# DCMotorControl_v01.net
KiCad netlist of a schematic drawn in EAGLE
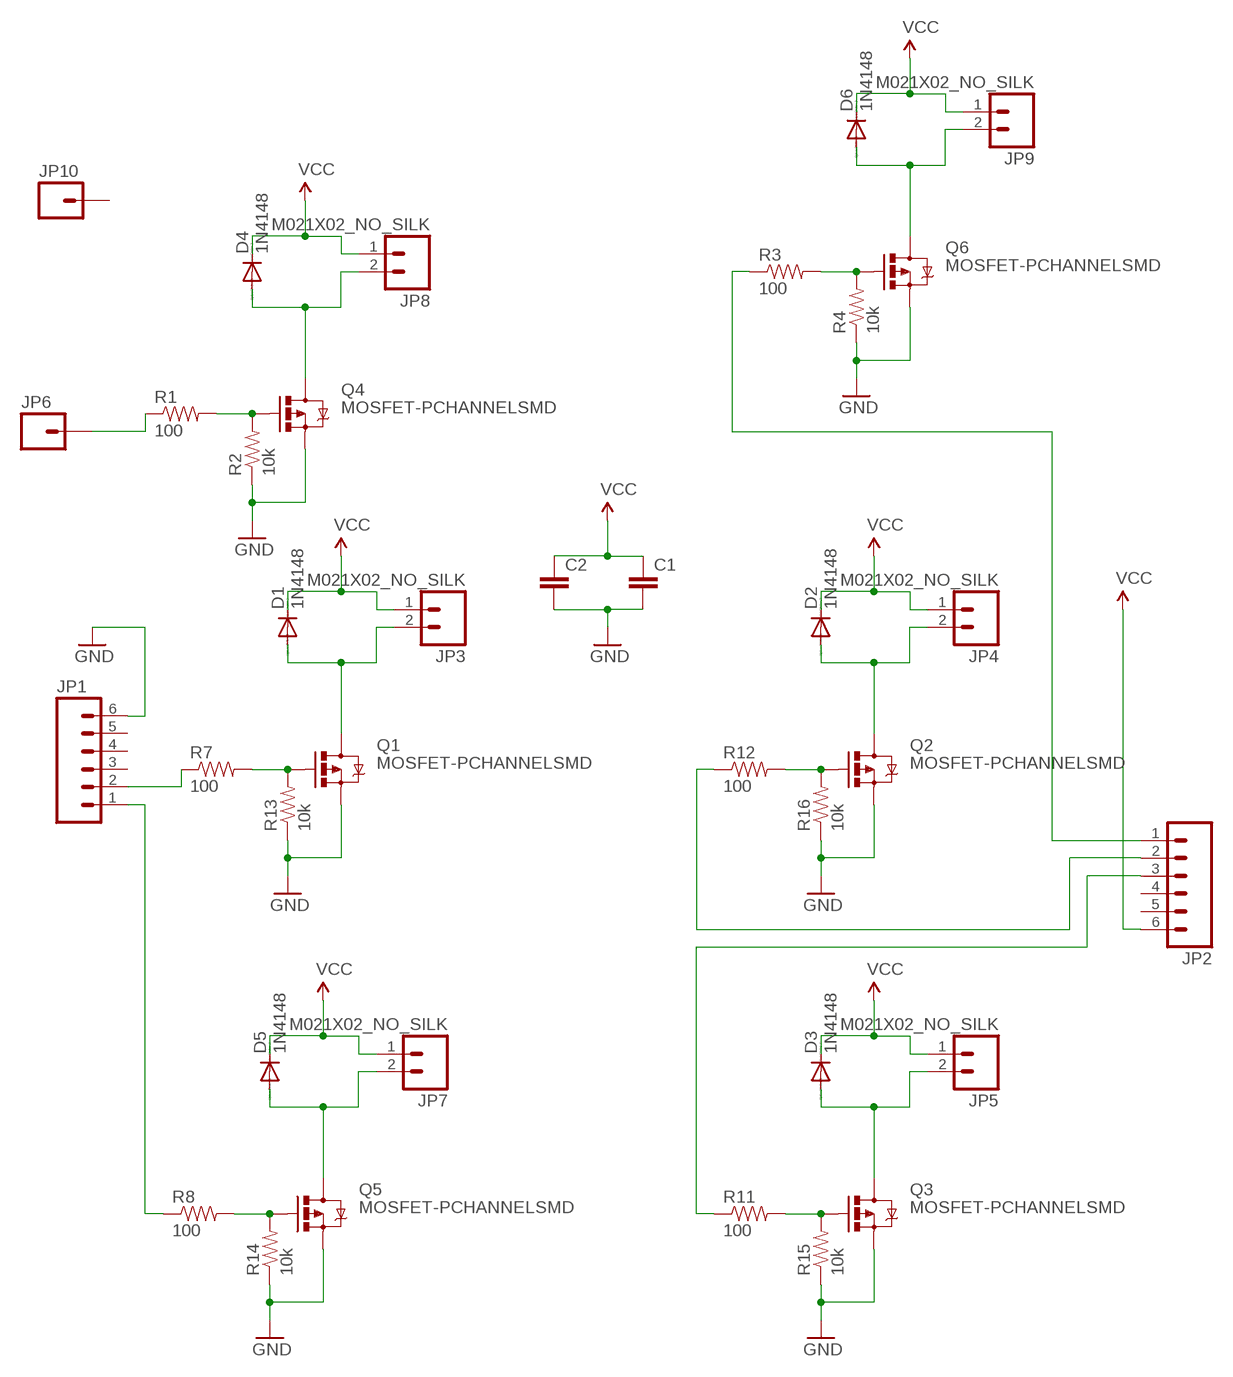
[diagram p0: schematic, sheet 1]

(export (version "E")
  (design (tool "Eeschema 10.0.6"))
  (components
    (comp (ref "C1")
      (value "CAP0805")
      (footprint "eagle-import:0805")
      (libsource (lib "eagle-import") (part "CAP0805"))
    )
    (comp (ref "C2")
      (value "CAP0805")
      (footprint "eagle-import:0805")
      (libsource (lib "eagle-import") (part "CAP0805"))
    )
    (comp (ref "D1")
      (value "1N4148")
      (footprint "eagle-import:SOD323-R")
      (libsource (lib "eagle-import") (part "DIODE-SOD323-R"))
    )
    (comp (ref "D2")
      (value "1N4148")
      (footprint "eagle-import:SOD323-R")
      (libsource (lib "eagle-import") (part "DIODE-SOD323-R"))
    )
    (comp (ref "D3")
      (value "1N4148")
      (footprint "eagle-import:SOD323-R")
      (libsource (lib "eagle-import") (part "DIODE-SOD323-R"))
    )
    (comp (ref "D4")
      (value "1N4148")
      (footprint "eagle-import:SOD323-R")
      (libsource (lib "eagle-import") (part "DIODE-SOD323-R"))
    )
    (comp (ref "D5")
      (value "1N4148")
      (footprint "eagle-import:SOD323-R")
      (libsource (lib "eagle-import") (part "DIODE-SOD323-R"))
    )
    (comp (ref "D6")
      (value "1N4148")
      (footprint "eagle-import:SOD323-R")
      (libsource (lib "eagle-import") (part "DIODE-SOD323-R"))
    )
    (comp (ref "JP1")
      (value "M06NO_SILK")
      (footprint "eagle-import:1X06_NO_SILK")
      (libsource (lib "eagle-import") (part "M06NO_SILK"))
    )
    (comp (ref "JP2")
      (value "M06NO_SILK")
      (footprint "eagle-import:1X06_NO_SILK")
      (libsource (lib "eagle-import") (part "M06NO_SILK"))
    )
    (comp (ref "JP3")
      (value "M021X02_NO_SILK")
      (footprint "eagle-import:1X02_NO_SILK")
      (libsource (lib "eagle-import") (part "M021X02_NO_SILK"))
    )
    (comp (ref "JP4")
      (value "M021X02_NO_SILK")
      (footprint "eagle-import:1X02_NO_SILK")
      (libsource (lib "eagle-import") (part "M021X02_NO_SILK"))
    )
    (comp (ref "JP5")
      (value "M021X02_NO_SILK")
      (footprint "eagle-import:1X02_NO_SILK")
      (libsource (lib "eagle-import") (part "M021X02_NO_SILK"))
    )
    (comp (ref "JP6")
      (value "M01NOSILK-KIT")
      (footprint "eagle-import:1X01NS-KIT")
      (libsource (lib "eagle-import") (part "M01NOSILK-KIT"))
    )
    (comp (ref "JP7")
      (value "M021X02_NO_SILK")
      (footprint "eagle-import:1X02_NO_SILK")
      (libsource (lib "eagle-import") (part "M021X02_NO_SILK"))
    )
    (comp (ref "JP8")
      (value "M021X02_NO_SILK")
      (footprint "eagle-import:1X02_NO_SILK")
      (libsource (lib "eagle-import") (part "M021X02_NO_SILK"))
    )
    (comp (ref "JP9")
      (value "M021X02_NO_SILK")
      (footprint "eagle-import:1X02_NO_SILK")
      (libsource (lib "eagle-import") (part "M021X02_NO_SILK"))
    )
    (comp (ref "JP10")
      (value "M01NOSILK-KIT")
      (footprint "eagle-import:1X01NS-KIT")
      (libsource (lib "eagle-import") (part "M01NOSILK-KIT"))
    )
    (comp (ref "Q1")
      (value "MOSFET-PCHANNELSMD")
      (footprint "eagle-import:SOT23-3")
      (libsource (lib "eagle-import") (part "MOSFET-PCHANNELSMD"))
    )
    (comp (ref "Q2")
      (value "MOSFET-PCHANNELSMD")
      (footprint "eagle-import:SOT23-3")
      (libsource (lib "eagle-import") (part "MOSFET-PCHANNELSMD"))
    )
    (comp (ref "Q3")
      (value "MOSFET-PCHANNELSMD")
      (footprint "eagle-import:SOT23-3")
      (libsource (lib "eagle-import") (part "MOSFET-PCHANNELSMD"))
    )
    (comp (ref "Q4")
      (value "MOSFET-PCHANNELSMD")
      (footprint "eagle-import:SOT23-3")
      (libsource (lib "eagle-import") (part "MOSFET-PCHANNELSMD"))
    )
    (comp (ref "Q5")
      (value "MOSFET-PCHANNELSMD")
      (footprint "eagle-import:SOT23-3")
      (libsource (lib "eagle-import") (part "MOSFET-PCHANNELSMD"))
    )
    (comp (ref "Q6")
      (value "MOSFET-PCHANNELSMD")
      (footprint "eagle-import:SOT23-3")
      (libsource (lib "eagle-import") (part "MOSFET-PCHANNELSMD"))
    )
    (comp (ref "R1")
      (value "100")
      (footprint "eagle-import:0603-RES")
      (libsource (lib "eagle-import") (part "RESISTOR0603-RES"))
    )
    (comp (ref "R2")
      (value "10k")
      (footprint "eagle-import:0603-RES")
      (libsource (lib "eagle-import") (part "RESISTOR0603-RES"))
    )
    (comp (ref "R3")
      (value "100")
      (footprint "eagle-import:0603-RES")
      (libsource (lib "eagle-import") (part "RESISTOR0603-RES"))
    )
    (comp (ref "R4")
      (value "10k")
      (footprint "eagle-import:0603-RES")
      (libsource (lib "eagle-import") (part "RESISTOR0603-RES"))
    )
    (comp (ref "R7")
      (value "100")
      (footprint "eagle-import:0603-RES")
      (libsource (lib "eagle-import") (part "RESISTOR0603-RES"))
    )
    (comp (ref "R8")
      (value "100")
      (footprint "eagle-import:0603-RES")
      (libsource (lib "eagle-import") (part "RESISTOR0603-RES"))
    )
    (comp (ref "R11")
      (value "100")
      (footprint "eagle-import:0603-RES")
      (libsource (lib "eagle-import") (part "RESISTOR0603-RES"))
    )
    (comp (ref "R12")
      (value "100")
      (footprint "eagle-import:0603-RES")
      (libsource (lib "eagle-import") (part "RESISTOR0603-RES"))
    )
    (comp (ref "R13")
      (value "10k")
      (footprint "eagle-import:0603-RES")
      (libsource (lib "eagle-import") (part "RESISTOR0603-RES"))
    )
    (comp (ref "R14")
      (value "10k")
      (footprint "eagle-import:0603-RES")
      (libsource (lib "eagle-import") (part "RESISTOR0603-RES"))
    )
    (comp (ref "R15")
      (value "10k")
      (footprint "eagle-import:0603-RES")
      (libsource (lib "eagle-import") (part "RESISTOR0603-RES"))
    )
    (comp (ref "R16")
      (value "10k")
      (footprint "eagle-import:0603-RES")
      (libsource (lib "eagle-import") (part "RESISTOR0603-RES"))
    )
  )
  (nets
    (net (code "1") (name "GND") (class "Default")
      (node (ref "C1") (pin "2") (pinfunction "2_2") (pintype "passive"))
      (node (ref "C2") (pin "2") (pinfunction "2_2") (pintype "passive"))
      (node (ref "JP1") (pin "6") (pinfunction "6_6") (pintype "passive"))
      (node (ref "Q1") (pin "2") (pinfunction "S_2") (pintype "passive"))
      (node (ref "Q2") (pin "2") (pinfunction "S_2") (pintype "passive"))
      (node (ref "Q3") (pin "2") (pinfunction "S_2") (pintype "passive"))
      (node (ref "Q4") (pin "2") (pinfunction "S_2") (pintype "passive"))
      (node (ref "Q5") (pin "2") (pinfunction "S_2") (pintype "passive"))
      (node (ref "Q6") (pin "2") (pinfunction "S_2") (pintype "passive"))
      (node (ref "R13") (pin "1") (pinfunction "1_1") (pintype "passive"))
      (node (ref "R14") (pin "1") (pinfunction "1_1") (pintype "passive"))
      (node (ref "R15") (pin "1") (pinfunction "1_1") (pintype "passive"))
      (node (ref "R16") (pin "1") (pinfunction "1_1") (pintype "passive"))
      (node (ref "R2") (pin "1") (pinfunction "1_1") (pintype "passive"))
      (node (ref "R4") (pin "1") (pinfunction "1_1") (pintype "passive"))
    )
    (net (code "2") (name "Net-(JP1-Pad1)") (class "Default")
      (node (ref "JP1") (pin "1") (pinfunction "1_1") (pintype "passive"))
      (node (ref "R8") (pin "1") (pinfunction "1_1") (pintype "passive"))
    )
    (net (code "3") (name "Net-(JP1-Pad2)") (class "Default")
      (node (ref "JP1") (pin "2") (pinfunction "2_2") (pintype "passive"))
      (node (ref "R7") (pin "1") (pinfunction "1_1") (pintype "passive"))
    )
    (net (code "4") (name "Net-(JP2-Pad1)") (class "Default")
      (node (ref "JP2") (pin "1") (pinfunction "1_1") (pintype "passive"))
      (node (ref "R3") (pin "1") (pinfunction "1_1") (pintype "passive"))
    )
    (net (code "5") (name "Net-(JP2-Pad2)") (class "Default")
      (node (ref "JP2") (pin "2") (pinfunction "2_2") (pintype "passive"))
      (node (ref "R12") (pin "1") (pinfunction "1_1") (pintype "passive"))
    )
    (net (code "6") (name "Net-(JP2-Pad3)") (class "Default")
      (node (ref "JP2") (pin "3") (pinfunction "3_3") (pintype "passive"))
      (node (ref "R11") (pin "1") (pinfunction "1_1") (pintype "passive"))
    )
    (net (code "7") (name "Net-(JP6-Pad1)") (class "Default")
      (node (ref "JP6") (pin "1") (pinfunction "1_1") (pintype "passive"))
      (node (ref "R1") (pin "1") (pinfunction "1_1") (pintype "passive"))
    )
    (net (code "8") (name "Net-(Q1-D)") (class "Default")
      (node (ref "D1") (pin "A") (pinfunction "A_A") (pintype "passive"))
      (node (ref "JP3") (pin "2") (pinfunction "2_2") (pintype "passive"))
      (node (ref "Q1") (pin "3") (pinfunction "D_3") (pintype "passive"))
    )
    (net (code "9") (name "Net-(Q1-G)") (class "Default")
      (node (ref "Q1") (pin "1") (pinfunction "G_1") (pintype "passive"))
      (node (ref "R13") (pin "2") (pinfunction "2_2") (pintype "passive"))
      (node (ref "R7") (pin "2") (pinfunction "2_2") (pintype "passive"))
    )
    (net (code "10") (name "Net-(Q2-D)") (class "Default")
      (node (ref "D2") (pin "A") (pinfunction "A_A") (pintype "passive"))
      (node (ref "JP4") (pin "2") (pinfunction "2_2") (pintype "passive"))
      (node (ref "Q2") (pin "3") (pinfunction "D_3") (pintype "passive"))
    )
    (net (code "11") (name "Net-(Q2-G)") (class "Default")
      (node (ref "Q2") (pin "1") (pinfunction "G_1") (pintype "passive"))
      (node (ref "R12") (pin "2") (pinfunction "2_2") (pintype "passive"))
      (node (ref "R16") (pin "2") (pinfunction "2_2") (pintype "passive"))
    )
    (net (code "12") (name "Net-(Q3-D)") (class "Default")
      (node (ref "D3") (pin "A") (pinfunction "A_A") (pintype "passive"))
      (node (ref "JP5") (pin "2") (pinfunction "2_2") (pintype "passive"))
      (node (ref "Q3") (pin "3") (pinfunction "D_3") (pintype "passive"))
    )
    (net (code "13") (name "Net-(Q3-G)") (class "Default")
      (node (ref "Q3") (pin "1") (pinfunction "G_1") (pintype "passive"))
      (node (ref "R11") (pin "2") (pinfunction "2_2") (pintype "passive"))
      (node (ref "R15") (pin "2") (pinfunction "2_2") (pintype "passive"))
    )
    (net (code "14") (name "Net-(Q4-D)") (class "Default")
      (node (ref "D4") (pin "A") (pinfunction "A_A") (pintype "passive"))
      (node (ref "JP8") (pin "2") (pinfunction "2_2") (pintype "passive"))
      (node (ref "Q4") (pin "3") (pinfunction "D_3") (pintype "passive"))
    )
    (net (code "15") (name "Net-(Q4-G)") (class "Default")
      (node (ref "Q4") (pin "1") (pinfunction "G_1") (pintype "passive"))
      (node (ref "R1") (pin "2") (pinfunction "2_2") (pintype "passive"))
      (node (ref "R2") (pin "2") (pinfunction "2_2") (pintype "passive"))
    )
    (net (code "16") (name "Net-(Q5-D)") (class "Default")
      (node (ref "D5") (pin "A") (pinfunction "A_A") (pintype "passive"))
      (node (ref "JP7") (pin "2") (pinfunction "2_2") (pintype "passive"))
      (node (ref "Q5") (pin "3") (pinfunction "D_3") (pintype "passive"))
    )
    (net (code "17") (name "Net-(Q5-G)") (class "Default")
      (node (ref "Q5") (pin "1") (pinfunction "G_1") (pintype "passive"))
      (node (ref "R14") (pin "2") (pinfunction "2_2") (pintype "passive"))
      (node (ref "R8") (pin "2") (pinfunction "2_2") (pintype "passive"))
    )
    (net (code "18") (name "Net-(Q6-D)") (class "Default")
      (node (ref "D6") (pin "A") (pinfunction "A_A") (pintype "passive"))
      (node (ref "JP9") (pin "2") (pinfunction "2_2") (pintype "passive"))
      (node (ref "Q6") (pin "3") (pinfunction "D_3") (pintype "passive"))
    )
    (net (code "19") (name "Net-(Q6-G)") (class "Default")
      (node (ref "Q6") (pin "1") (pinfunction "G_1") (pintype "passive"))
      (node (ref "R3") (pin "2") (pinfunction "2_2") (pintype "passive"))
      (node (ref "R4") (pin "2") (pinfunction "2_2") (pintype "passive"))
    )
    (net (code "20") (name "VCC") (class "Default")
      (node (ref "C1") (pin "1") (pinfunction "1_1") (pintype "passive"))
      (node (ref "C2") (pin "1") (pinfunction "1_1") (pintype "passive"))
      (node (ref "D1") (pin "C") (pinfunction "C_C") (pintype "passive"))
      (node (ref "D2") (pin "C") (pinfunction "C_C") (pintype "passive"))
      (node (ref "D3") (pin "C") (pinfunction "C_C") (pintype "passive"))
      (node (ref "D4") (pin "C") (pinfunction "C_C") (pintype "passive"))
      (node (ref "D5") (pin "C") (pinfunction "C_C") (pintype "passive"))
      (node (ref "D6") (pin "C") (pinfunction "C_C") (pintype "passive"))
      (node (ref "JP2") (pin "6") (pinfunction "6_6") (pintype "passive"))
      (node (ref "JP3") (pin "1") (pinfunction "1_1") (pintype "passive"))
      (node (ref "JP4") (pin "1") (pinfunction "1_1") (pintype "passive"))
      (node (ref "JP5") (pin "1") (pinfunction "1_1") (pintype "passive"))
      (node (ref "JP7") (pin "1") (pinfunction "1_1") (pintype "passive"))
      (node (ref "JP8") (pin "1") (pinfunction "1_1") (pintype "passive"))
      (node (ref "JP9") (pin "1") (pinfunction "1_1") (pintype "passive"))
    )
    (net (code "21") (name "unconnected-(JP1-Pad3)") (class "Default")
      (node (ref "JP1") (pin "3") (pinfunction "3_3") (pintype "passive"))
    )
    (net (code "22") (name "unconnected-(JP1-Pad4)") (class "Default")
      (node (ref "JP1") (pin "4") (pinfunction "4_4") (pintype "passive"))
    )
    (net (code "23") (name "unconnected-(JP1-Pad5)") (class "Default")
      (node (ref "JP1") (pin "5") (pinfunction "5_5") (pintype "passive"))
    )
    (net (code "24") (name "unconnected-(JP2-Pad4)") (class "Default")
      (node (ref "JP2") (pin "4") (pinfunction "4_4") (pintype "passive"))
    )
    (net (code "25") (name "unconnected-(JP2-Pad5)") (class "Default")
      (node (ref "JP2") (pin "5") (pinfunction "5_5") (pintype "passive"))
    )
    (net (code "26") (name "unconnected-(JP10-Pad1)") (class "Default")
      (node (ref "JP10") (pin "1") (pinfunction "1_1") (pintype "passive"))
    )
  )
)
